# lichtenstein_onion.net
KiCad netlist of a schematic drawn in EAGLE
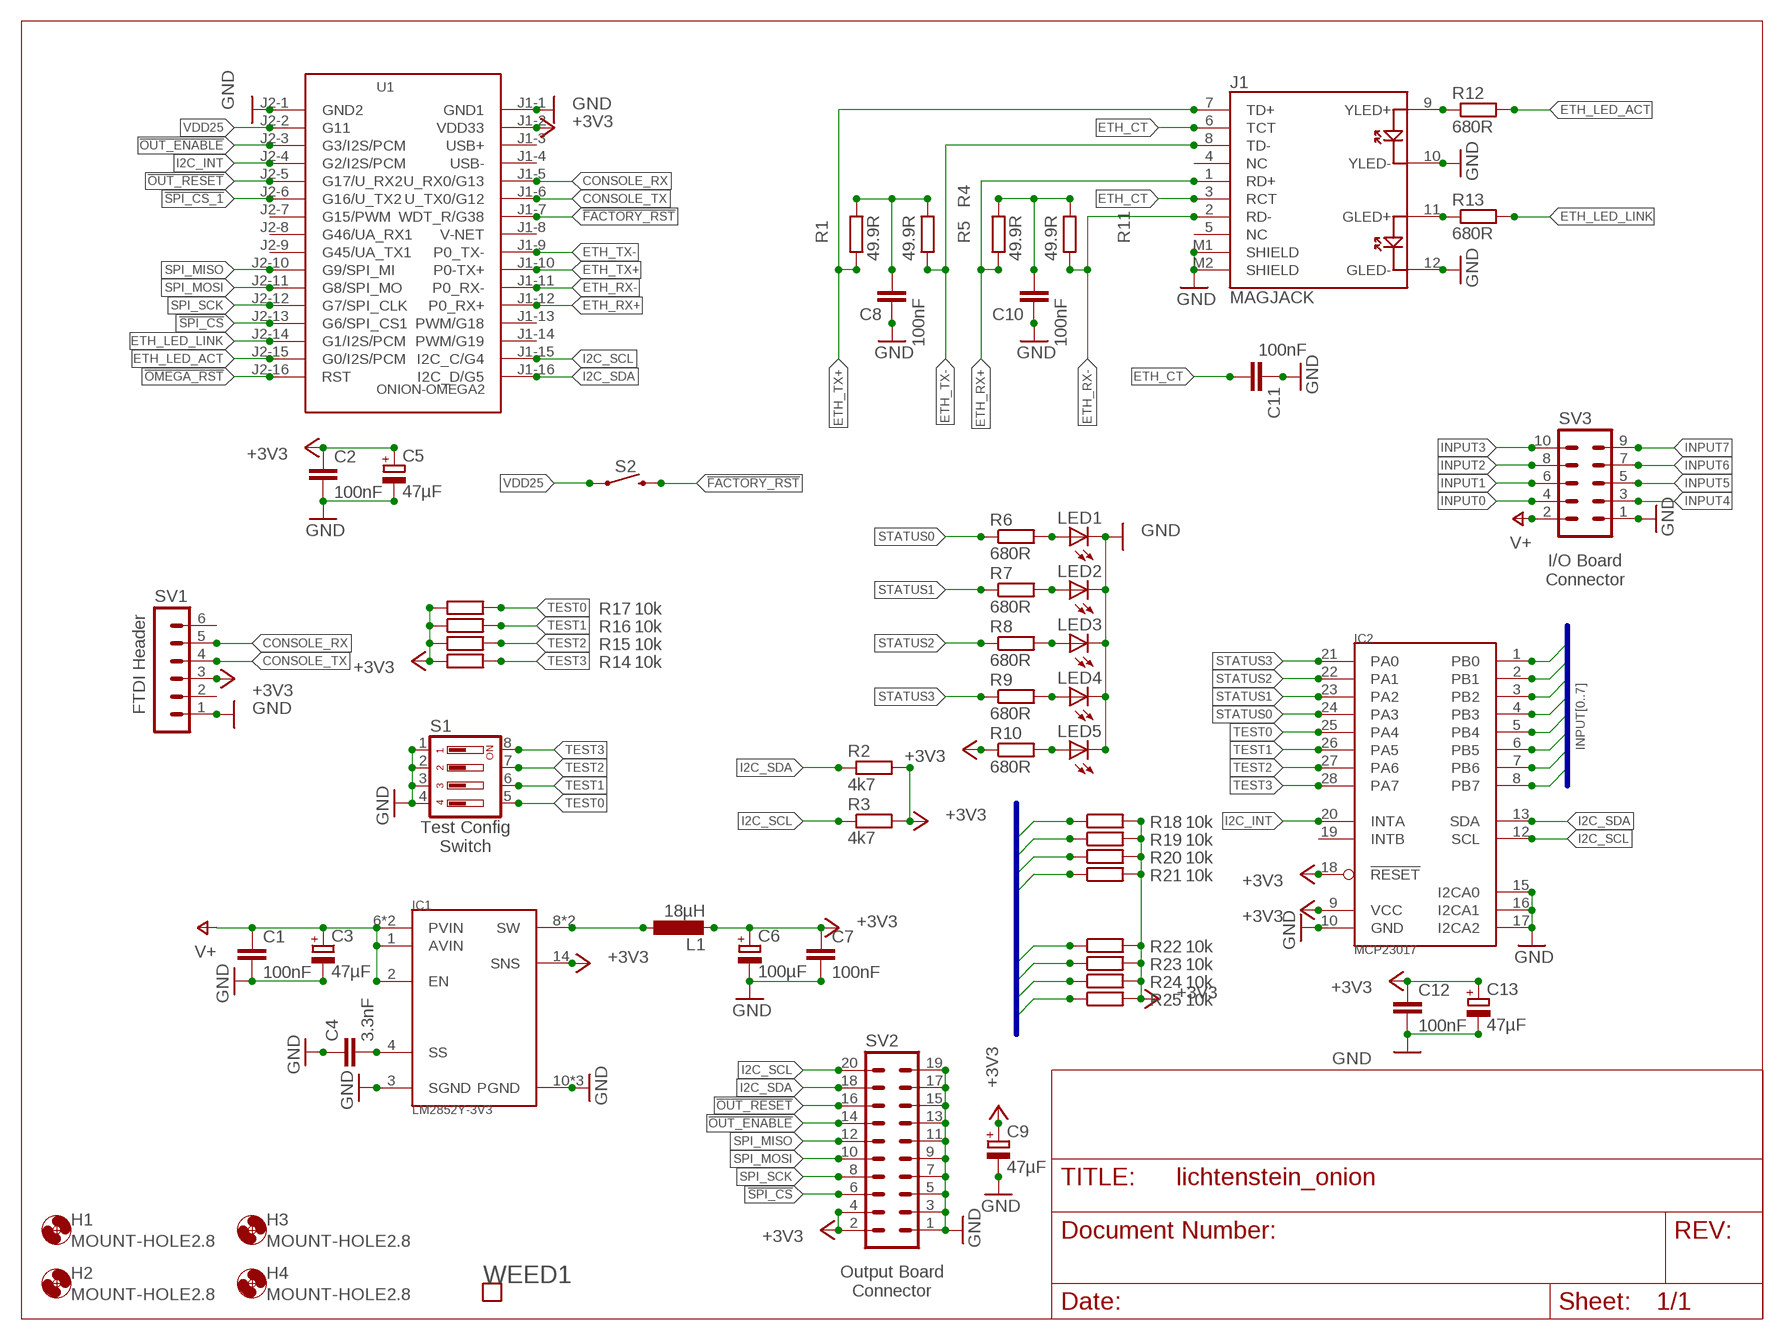
[diagram p0: schematic, sheet 1]

(export (version "E")
  (design (tool "Eeschema 10.0.6"))
  (components
    (comp (ref "C1")
      (value "100nF")
      (footprint "eagle-import:C0805")
      (libsource (lib "eagle-import") (part "C-EUC0805"))
    )
    (comp (ref "C2")
      (value "100nF")
      (footprint "eagle-import:C0805")
      (libsource (lib "eagle-import") (part "C-EUC0805"))
    )
    (comp (ref "C3")
      (value "47µF")
      (footprint "eagle-import:CT7343")
      (libsource (lib "eagle-import") (part "CPOL-EUCT7343"))
    )
    (comp (ref "C4")
      (value "3.3nF")
      (footprint "eagle-import:C0805")
      (libsource (lib "eagle-import") (part "C-EUC0805"))
    )
    (comp (ref "C5")
      (value "47µF")
      (footprint "eagle-import:CT7343")
      (libsource (lib "eagle-import") (part "CPOL-EUCT7343"))
    )
    (comp (ref "C6")
      (value "100µF")
      (footprint "eagle-import:CT7343")
      (libsource (lib "eagle-import") (part "CPOL-EUCT7343"))
    )
    (comp (ref "C7")
      (value "100nF")
      (footprint "eagle-import:C0805")
      (libsource (lib "eagle-import") (part "C-EUC0805"))
    )
    (comp (ref "C8")
      (value "100nF")
      (footprint "eagle-import:C0805")
      (libsource (lib "eagle-import") (part "C-EUC0805"))
    )
    (comp (ref "C9")
      (value "47µF")
      (footprint "eagle-import:SMC_D")
      (libsource (lib "eagle-import") (part "CPOL-EUSMCD"))
    )
    (comp (ref "C10")
      (value "100nF")
      (footprint "eagle-import:C0805")
      (libsource (lib "eagle-import") (part "C-EUC0805"))
    )
    (comp (ref "C11")
      (value "100nF")
      (footprint "eagle-import:C0805")
      (libsource (lib "eagle-import") (part "C-EUC0805"))
    )
    (comp (ref "C12")
      (value "100nF")
      (footprint "eagle-import:C0805")
      (libsource (lib "eagle-import") (part "C-EUC0805"))
    )
    (comp (ref "C13")
      (value "47µF")
      (footprint "eagle-import:CT7343")
      (libsource (lib "eagle-import") (part "CPOL-EUCT7343"))
    )
    (comp (ref "H1")
      (value "MOUNT-HOLE2.8")
      (footprint "eagle-import:2,8")
      (libsource (lib "eagle-import") (part "MOUNT-HOLE2.8"))
    )
    (comp (ref "H2")
      (value "MOUNT-HOLE2.8")
      (footprint "eagle-import:2,8")
      (libsource (lib "eagle-import") (part "MOUNT-HOLE2.8"))
    )
    (comp (ref "H3")
      (value "MOUNT-HOLE2.8")
      (footprint "eagle-import:2,8")
      (libsource (lib "eagle-import") (part "MOUNT-HOLE2.8"))
    )
    (comp (ref "H4")
      (value "MOUNT-HOLE2.8")
      (footprint "eagle-import:2,8")
      (libsource (lib "eagle-import") (part "MOUNT-HOLE2.8"))
    )
    (comp (ref "IC1")
      (value "LM2852Y-3V3")
      (footprint "eagle-import:HTSSOP14")
      (libsource (lib "eagle-import") (part "LM2852HTSSOP14"))
    )
    (comp (ref "IC2")
      (value "MCP23017")
      (footprint "eagle-import:SSOP28")
      (libsource (lib "eagle-import") (part "MCP23017SSOP28"))
    )
    (comp (ref "J1")
      (value "MAGJACK")
      (footprint "eagle-import:MAGJACK")
      (libsource (lib "eagle-import") (part "MAGJACK"))
    )
    (comp (ref "L1")
      (value "18µH")
      (footprint "eagle-import:SRR1050A")
      (libsource (lib "eagle-import") (part "SRR1050A"))
    )
    (comp (ref "LED1")
      (value "LEDCHIPLED_1206")
      (footprint "eagle-import:CHIPLED_1206")
      (libsource (lib "eagle-import") (part "LEDCHIPLED_1206"))
    )
    (comp (ref "LED2")
      (value "LEDCHIPLED_1206")
      (footprint "eagle-import:CHIPLED_1206")
      (libsource (lib "eagle-import") (part "LEDCHIPLED_1206"))
    )
    (comp (ref "LED3")
      (value "LEDCHIPLED_1206")
      (footprint "eagle-import:CHIPLED_1206")
      (libsource (lib "eagle-import") (part "LEDCHIPLED_1206"))
    )
    (comp (ref "LED4")
      (value "LEDCHIPLED_1206")
      (footprint "eagle-import:CHIPLED_1206")
      (libsource (lib "eagle-import") (part "LEDCHIPLED_1206"))
    )
    (comp (ref "LED5")
      (value "LEDCHIPLED_1206")
      (footprint "eagle-import:CHIPLED_1206")
      (libsource (lib "eagle-import") (part "LEDCHIPLED_1206"))
    )
    (comp (ref "R1")
      (value "49.9R")
      (footprint "eagle-import:M0805")
      (libsource (lib "eagle-import") (part "R-EU_M0805"))
    )
    (comp (ref "R2")
      (value "4k7")
      (footprint "eagle-import:M0805")
      (libsource (lib "eagle-import") (part "R-EU_M0805"))
    )
    (comp (ref "R3")
      (value "4k7")
      (footprint "eagle-import:M0805")
      (libsource (lib "eagle-import") (part "R-EU_M0805"))
    )
    (comp (ref "R4")
      (value "49.9R")
      (footprint "eagle-import:M0805")
      (libsource (lib "eagle-import") (part "R-EU_M0805"))
    )
    (comp (ref "R5")
      (value "49.9R")
      (footprint "eagle-import:M0805")
      (libsource (lib "eagle-import") (part "R-EU_M0805"))
    )
    (comp (ref "R6")
      (value "680R")
      (footprint "eagle-import:M0805")
      (libsource (lib "eagle-import") (part "R-EU_M0805"))
    )
    (comp (ref "R7")
      (value "680R")
      (footprint "eagle-import:M0805")
      (libsource (lib "eagle-import") (part "R-EU_M0805"))
    )
    (comp (ref "R8")
      (value "680R")
      (footprint "eagle-import:M0805")
      (libsource (lib "eagle-import") (part "R-EU_M0805"))
    )
    (comp (ref "R9")
      (value "680R")
      (footprint "eagle-import:M0805")
      (libsource (lib "eagle-import") (part "R-EU_M0805"))
    )
    (comp (ref "R10")
      (value "680R")
      (footprint "eagle-import:M0805")
      (libsource (lib "eagle-import") (part "R-EU_M0805"))
    )
    (comp (ref "R11")
      (value "49.9R")
      (footprint "eagle-import:M0805")
      (libsource (lib "eagle-import") (part "R-EU_M0805"))
    )
    (comp (ref "R12")
      (value "680R")
      (footprint "eagle-import:M0805")
      (libsource (lib "eagle-import") (part "R-EU_M0805"))
    )
    (comp (ref "R13")
      (value "680R")
      (footprint "eagle-import:M0805")
      (libsource (lib "eagle-import") (part "R-EU_M0805"))
    )
    (comp (ref "R14")
      (value "10k")
      (footprint "eagle-import:M0805")
      (libsource (lib "eagle-import") (part "R-EU_M0805"))
    )
    (comp (ref "R15")
      (value "10k")
      (footprint "eagle-import:M0805")
      (libsource (lib "eagle-import") (part "R-EU_M0805"))
    )
    (comp (ref "R16")
      (value "10k")
      (footprint "eagle-import:M0805")
      (libsource (lib "eagle-import") (part "R-EU_M0805"))
    )
    (comp (ref "R17")
      (value "10k")
      (footprint "eagle-import:M0805")
      (libsource (lib "eagle-import") (part "R-EU_M0805"))
    )
    (comp (ref "R18")
      (value "10k")
      (footprint "eagle-import:M0805")
      (libsource (lib "eagle-import") (part "R-EU_M0805"))
    )
    (comp (ref "R19")
      (value "10k")
      (footprint "eagle-import:M0805")
      (libsource (lib "eagle-import") (part "R-EU_M0805"))
    )
    (comp (ref "R20")
      (value "10k")
      (footprint "eagle-import:M0805")
      (libsource (lib "eagle-import") (part "R-EU_M0805"))
    )
    (comp (ref "R21")
      (value "10k")
      (footprint "eagle-import:M0805")
      (libsource (lib "eagle-import") (part "R-EU_M0805"))
    )
    (comp (ref "R22")
      (value "10k")
      (footprint "eagle-import:M0805")
      (libsource (lib "eagle-import") (part "R-EU_M0805"))
    )
    (comp (ref "R23")
      (value "10k")
      (footprint "eagle-import:M0805")
      (libsource (lib "eagle-import") (part "R-EU_M0805"))
    )
    (comp (ref "R24")
      (value "10k")
      (footprint "eagle-import:M0805")
      (libsource (lib "eagle-import") (part "R-EU_M0805"))
    )
    (comp (ref "R25")
      (value "10k")
      (footprint "eagle-import:M0805")
      (libsource (lib "eagle-import") (part "R-EU_M0805"))
    )
    (comp (ref "S1")
      (value "219-04")
      (footprint "eagle-import:CTS-219-04")
      (libsource (lib "eagle-import") (part "219-04"))
    )
    (comp (ref "S2")
      (value "MOMENTARY-SWITCH-SPST-PTH-6.0MM")
      (footprint "eagle-import:TACTILE_SWITCH_PTH_6.0MM")
      (libsource (lib "eagle-import") (part "MOMENTARY-SWITCH-SPST-PTH-6.0MM"))
    )
    (comp (ref "SV1")
      (value "MA06-1")
      (footprint "eagle-import:MA06-1")
      (libsource (lib "eagle-import") (part "MA06-1"))
    )
    (comp (ref "SV2")
      (value "MA10-2")
      (footprint "eagle-import:MA10-2")
      (libsource (lib "eagle-import") (part "MA10-2"))
    )
    (comp (ref "SV3")
      (value "MA05-2")
      (footprint "eagle-import:MA05-2")
      (libsource (lib "eagle-import") (part "MA05-2"))
    )
    (comp (ref "U1")
      (value "ONION-OMEGA2")
      (footprint "eagle-import:ONION-2MM-2X16")
      (libsource (lib "eagle-import") (part "ONION-OMEGA2"))
    )
    (comp (ref "WEED1")
      (value "WEED")
      (footprint "eagle-import:DOINK")
      (libsource (lib "eagle-import") (part "WEED"))
    )
  )
  (nets
    (net (code "1") (name "+3V3") (class "Default")
      (node (ref "C12") (pin "1") (pinfunction "1_1") (pintype "passive"))
      (node (ref "C13") (pin "+") (pinfunction "+_+") (pintype "passive"))
      (node (ref "C2") (pin "1") (pinfunction "1_1") (pintype "passive"))
      (node (ref "C5") (pin "+") (pinfunction "+_+") (pintype "passive"))
      (node (ref "C6") (pin "+") (pinfunction "+_+") (pintype "passive"))
      (node (ref "C7") (pin "1") (pinfunction "1_1") (pintype "passive"))
      (node (ref "C9") (pin "+") (pinfunction "+_+") (pintype "passive"))
      (node (ref "IC1") (pin "14") (pinfunction "SNS_14") (pintype "bidirectional"))
      (node (ref "IC2") (pin "18") (pinfunction "~{RESET}_18") (pintype "input"))
      (node (ref "IC2") (pin "9") (pinfunction "VCC_9") (pintype "power_in"))
      (node (ref "L1") (pin "P$2") (pinfunction "2_P$2") (pintype "passive"))
      (node (ref "R10") (pin "1") (pinfunction "1_1") (pintype "passive"))
      (node (ref "R14") (pin "1") (pinfunction "1_1") (pintype "passive"))
      (node (ref "R15") (pin "1") (pinfunction "1_1") (pintype "passive"))
      (node (ref "R16") (pin "1") (pinfunction "1_1") (pintype "passive"))
      (node (ref "R17") (pin "1") (pinfunction "1_1") (pintype "passive"))
      (node (ref "R18") (pin "2") (pinfunction "2_2") (pintype "passive"))
      (node (ref "R19") (pin "2") (pinfunction "2_2") (pintype "passive"))
      (node (ref "R2") (pin "2") (pinfunction "2_2") (pintype "passive"))
      (node (ref "R20") (pin "2") (pinfunction "2_2") (pintype "passive"))
      (node (ref "R21") (pin "2") (pinfunction "2_2") (pintype "passive"))
      (node (ref "R22") (pin "2") (pinfunction "2_2") (pintype "passive"))
      (node (ref "R23") (pin "2") (pinfunction "2_2") (pintype "passive"))
      (node (ref "R24") (pin "2") (pinfunction "2_2") (pintype "passive"))
      (node (ref "R25") (pin "2") (pinfunction "2_2") (pintype "passive"))
      (node (ref "R3") (pin "2") (pinfunction "2_2") (pintype "passive"))
      (node (ref "SV1") (pin "3") (pinfunction "3_3") (pintype "passive"))
      (node (ref "SV2") (pin "2") (pinfunction "2_2") (pintype "passive"))
      (node (ref "SV2") (pin "4") (pinfunction "4_4") (pintype "passive"))
      (node (ref "U1") (pin "J1-2") (pinfunction "VDD33_J1-2") (pintype "bidirectional"))
    )
    (net (code "3") (name "/~{FACTORY_RST}") (class "Default")
      (node (ref "S2") (pin "3") (pinfunction "2_3") (pintype "passive"))
      (node (ref "U1") (pin "J1-7") (pinfunction "WDT_R/G38_J1-7") (pintype "bidirectional"))
    )
    (net (code "4") (name "/~{OMEGA_RST}") (class "Default")
      (node (ref "U1") (pin "J2-16") (pinfunction "RST_J2-16") (pintype "bidirectional"))
    )
    (net (code "5") (name "/~{OUT_ENABLE}") (class "Default")
      (node (ref "SV2") (pin "14") (pinfunction "14_14") (pintype "passive"))
      (node (ref "U1") (pin "J2-3") (pinfunction "G3/I2S/PCM_J2-3") (pintype "bidirectional"))
    )
    (net (code "6") (name "/~{OUT_RESET}") (class "Default")
      (node (ref "SV2") (pin "16") (pinfunction "16_16") (pintype "passive"))
      (node (ref "U1") (pin "J2-5") (pinfunction "G17/U_RX2_J2-5") (pintype "bidirectional"))
    )
    (net (code "7") (name "/~{SPI_CS_1}") (class "Default")
      (node (ref "U1") (pin "J2-6") (pinfunction "G16/U_TX2_J2-6") (pintype "bidirectional"))
    )
    (net (code "8") (name "/~{SPI_CS}") (class "Default")
      (node (ref "SV2") (pin "6") (pinfunction "6_6") (pintype "passive"))
      (node (ref "U1") (pin "J2-13") (pinfunction "G6/SPI_CS1_J2-13") (pintype "bidirectional"))
    )
    (net (code "9") (name "CONSOLE_RX") (class "Default")
      (node (ref "SV1") (pin "5") (pinfunction "5_5") (pintype "passive"))
      (node (ref "U1") (pin "J1-5") (pinfunction "U_RX0/G13_J1-5") (pintype "bidirectional"))
    )
    (net (code "10") (name "CONSOLE_TX") (class "Default")
      (node (ref "SV1") (pin "4") (pinfunction "4_4") (pintype "passive"))
      (node (ref "U1") (pin "J1-6") (pinfunction "U_TX0/G12_J1-6") (pintype "bidirectional"))
    )
    (net (code "11") (name "ETH_CT") (class "Default")
      (node (ref "C11") (pin "2") (pinfunction "2_2") (pintype "passive"))
      (node (ref "J1") (pin "3") (pinfunction "RCT_3") (pintype "bidirectional"))
      (node (ref "J1") (pin "6") (pinfunction "TCT_6") (pintype "bidirectional"))
    )
    (net (code "12") (name "ETH_LED_ACT") (class "Default")
      (node (ref "R12") (pin "2") (pinfunction "2_2") (pintype "passive"))
      (node (ref "U1") (pin "J2-15") (pinfunction "G0/I2S/PCM_J2-15") (pintype "bidirectional"))
    )
    (net (code "13") (name "ETH_LED_LINK") (class "Default")
      (node (ref "R13") (pin "2") (pinfunction "2_2") (pintype "passive"))
      (node (ref "U1") (pin "J2-14") (pinfunction "G1/I2S/PCM_J2-14") (pintype "bidirectional"))
    )
    (net (code "14") (name "ETH_RX+") (class "Default")
      (node (ref "J1") (pin "1") (pinfunction "RD+_1") (pintype "bidirectional"))
      (node (ref "R5") (pin "1") (pinfunction "1_1") (pintype "passive"))
      (node (ref "U1") (pin "J1-12") (pinfunction "P0_RX+_J1-12") (pintype "bidirectional"))
    )
    (net (code "15") (name "ETH_RX-") (class "Default")
      (node (ref "J1") (pin "2") (pinfunction "RD-_2") (pintype "bidirectional"))
      (node (ref "R11") (pin "1") (pinfunction "1_1") (pintype "passive"))
      (node (ref "U1") (pin "J1-11") (pinfunction "P0_RX-_J1-11") (pintype "bidirectional"))
    )
    (net (code "16") (name "ETH_TX+") (class "Default")
      (node (ref "J1") (pin "7") (pinfunction "TD+_7") (pintype "bidirectional"))
      (node (ref "R1") (pin "1") (pinfunction "1_1") (pintype "passive"))
      (node (ref "U1") (pin "J1-10") (pinfunction "P0-TX+_J1-10") (pintype "bidirectional"))
    )
    (net (code "17") (name "ETH_TX-") (class "Default")
      (node (ref "J1") (pin "8") (pinfunction "TD-_8") (pintype "bidirectional"))
      (node (ref "R4") (pin "1") (pinfunction "1_1") (pintype "passive"))
      (node (ref "U1") (pin "J1-9") (pinfunction "P0_TX-_J1-9") (pintype "bidirectional"))
    )
    (net (code "18") (name "GND") (class "Default")
      (node (ref "C1") (pin "2") (pinfunction "2_2") (pintype "passive"))
      (node (ref "C10") (pin "1") (pinfunction "1_1") (pintype "passive"))
      (node (ref "C11") (pin "1") (pinfunction "1_1") (pintype "passive"))
      (node (ref "C12") (pin "2") (pinfunction "2_2") (pintype "passive"))
      (node (ref "C13") (pin "-") (pinfunction "-_-") (pintype "passive"))
      (node (ref "C2") (pin "2") (pinfunction "2_2") (pintype "passive"))
      (node (ref "C3") (pin "-") (pinfunction "-_-") (pintype "passive"))
      (node (ref "C4") (pin "1") (pinfunction "1_1") (pintype "passive"))
      (node (ref "C5") (pin "-") (pinfunction "-_-") (pintype "passive"))
      (node (ref "C6") (pin "-") (pinfunction "-_-") (pintype "passive"))
      (node (ref "C7") (pin "2") (pinfunction "2_2") (pintype "passive"))
      (node (ref "C8") (pin "1") (pinfunction "1_1") (pintype "passive"))
      (node (ref "C9") (pin "-") (pinfunction "-_-") (pintype "passive"))
      (node (ref "IC1") (pin "10") (pinfunction "PGND_10") (pintype "power_in"))
      (node (ref "IC1") (pin "11") (pinfunction "PGND_11") (pintype "power_in"))
      (node (ref "IC1") (pin "3") (pinfunction "SGND_3") (pintype "power_in"))
      (node (ref "IC1") (pin "PAD") (pinfunction "PGND_PAD") (pintype "power_in"))
      (node (ref "IC2") (pin "10") (pinfunction "GND_10") (pintype "power_in"))
      (node (ref "IC2") (pin "15") (pinfunction "I2CA0_15") (pintype "bidirectional"))
      (node (ref "IC2") (pin "16") (pinfunction "I2CA1_16") (pintype "bidirectional"))
      (node (ref "IC2") (pin "17") (pinfunction "I2CA2_17") (pintype "bidirectional"))
      (node (ref "J1") (pin "10") (pinfunction "YLED-_10") (pintype "bidirectional"))
      (node (ref "J1") (pin "12") (pinfunction "GLED-_12") (pintype "bidirectional"))
      (node (ref "J1") (pin "M1") (pinfunction "SHIELD_M1") (pintype "bidirectional"))
      (node (ref "J1") (pin "M2") (pinfunction "SHIELD_M2") (pintype "bidirectional"))
      (node (ref "LED1") (pin "C") (pinfunction "C_C") (pintype "passive"))
      (node (ref "LED2") (pin "C") (pinfunction "C_C") (pintype "passive"))
      (node (ref "LED3") (pin "C") (pinfunction "C_C") (pintype "passive"))
      (node (ref "LED4") (pin "C") (pinfunction "C_C") (pintype "passive"))
      (node (ref "LED5") (pin "C") (pinfunction "C_C") (pintype "passive"))
      (node (ref "S1") (pin "1") (pinfunction "1_1") (pintype "passive"))
      (node (ref "S1") (pin "2") (pinfunction "2_2") (pintype "passive"))
      (node (ref "S1") (pin "3") (pinfunction "3_3") (pintype "passive"))
      (node (ref "S1") (pin "4") (pinfunction "4_4") (pintype "passive"))
      (node (ref "SV1") (pin "1") (pinfunction "1_1") (pintype "passive"))
      (node (ref "SV2") (pin "1") (pinfunction "1_1") (pintype "passive"))
      (node (ref "SV2") (pin "11") (pinfunction "11_11") (pintype "passive"))
      (node (ref "SV2") (pin "13") (pinfunction "13_13") (pintype "passive"))
      (node (ref "SV2") (pin "15") (pinfunction "15_15") (pintype "passive"))
      (node (ref "SV2") (pin "17") (pinfunction "17_17") (pintype "passive"))
      (node (ref "SV2") (pin "19") (pinfunction "19_19") (pintype "passive"))
      (node (ref "SV2") (pin "3") (pinfunction "3_3") (pintype "passive"))
      (node (ref "SV2") (pin "5") (pinfunction "5_5") (pintype "passive"))
      (node (ref "SV2") (pin "7") (pinfunction "7_7") (pintype "passive"))
      (node (ref "SV2") (pin "9") (pinfunction "9_9") (pintype "passive"))
      (node (ref "SV3") (pin "1") (pinfunction "1_1") (pintype "passive"))
      (node (ref "U1") (pin "J1-1") (pinfunction "GND1_J1-1") (pintype "bidirectional"))
      (node (ref "U1") (pin "J2-1") (pinfunction "GND2_J2-1") (pintype "bidirectional"))
    )
    (net (code "19") (name "I2C_INT") (class "Default")
      (node (ref "IC2") (pin "20") (pinfunction "INTA_20") (pintype "output"))
      (node (ref "U1") (pin "J2-4") (pinfunction "G2/I2S/PCM_J2-4") (pintype "bidirectional"))
    )
    (net (code "20") (name "I2C_SCL") (class "Default")
      (node (ref "IC2") (pin "12") (pinfunction "SCL_12") (pintype "bidirectional"))
      (node (ref "R3") (pin "1") (pinfunction "1_1") (pintype "passive"))
      (node (ref "SV2") (pin "20") (pinfunction "20_20") (pintype "passive"))
      (node (ref "U1") (pin "J1-15") (pinfunction "I2C_C/G4_J1-15") (pintype "bidirectional"))
    )
    (net (code "21") (name "I2C_SDA") (class "Default")
      (node (ref "IC2") (pin "13") (pinfunction "SDA_13") (pintype "bidirectional"))
      (node (ref "R2") (pin "1") (pinfunction "1_1") (pintype "passive"))
      (node (ref "SV2") (pin "18") (pinfunction "18_18") (pintype "passive"))
      (node (ref "U1") (pin "J1-16") (pinfunction "I2C_D/G5_J1-16") (pintype "bidirectional"))
    )
    (net (code "22") (name "INPUT0") (class "Default")
      (node (ref "IC2") (pin "2") (pinfunction "PB1_2") (pintype "bidirectional"))
      (node (ref "R18") (pin "1") (pinfunction "1_1") (pintype "passive"))
      (node (ref "SV3") (pin "4") (pinfunction "4_4") (pintype "passive"))
    )
    (net (code "23") (name "INPUT1") (class "Default")
      (node (ref "IC2") (pin "4") (pinfunction "PB3_4") (pintype "bidirectional"))
      (node (ref "R19") (pin "1") (pinfunction "1_1") (pintype "passive"))
      (node (ref "SV3") (pin "6") (pinfunction "6_6") (pintype "passive"))
    )
    (net (code "24") (name "INPUT2") (class "Default")
      (node (ref "IC2") (pin "6") (pinfunction "PB5_6") (pintype "bidirectional"))
      (node (ref "R24") (pin "1") (pinfunction "1_1") (pintype "passive"))
      (node (ref "SV3") (pin "8") (pinfunction "8_8") (pintype "passive"))
    )
    (net (code "25") (name "INPUT3") (class "Default")
      (node (ref "IC2") (pin "8") (pinfunction "PB7_8") (pintype "bidirectional"))
      (node (ref "R25") (pin "1") (pinfunction "1_1") (pintype "passive"))
      (node (ref "SV3") (pin "10") (pinfunction "10_10") (pintype "passive"))
    )
    (net (code "26") (name "INPUT4") (class "Default")
      (node (ref "IC2") (pin "1") (pinfunction "PB0_1") (pintype "bidirectional"))
      (node (ref "R20") (pin "1") (pinfunction "1_1") (pintype "passive"))
      (node (ref "SV3") (pin "3") (pinfunction "3_3") (pintype "passive"))
    )
    (net (code "27") (name "INPUT5") (class "Default")
      (node (ref "IC2") (pin "3") (pinfunction "PB2_3") (pintype "bidirectional"))
      (node (ref "R21") (pin "1") (pinfunction "1_1") (pintype "passive"))
      (node (ref "SV3") (pin "5") (pinfunction "5_5") (pintype "passive"))
    )
    (net (code "28") (name "INPUT6") (class "Default")
      (node (ref "IC2") (pin "5") (pinfunction "PB4_5") (pintype "bidirectional"))
      (node (ref "R23") (pin "1") (pinfunction "1_1") (pintype "passive"))
      (node (ref "SV3") (pin "7") (pinfunction "7_7") (pintype "passive"))
    )
    (net (code "29") (name "INPUT7") (class "Default")
      (node (ref "IC2") (pin "7") (pinfunction "PB6_7") (pintype "bidirectional"))
      (node (ref "R22") (pin "1") (pinfunction "1_1") (pintype "passive"))
      (node (ref "SV3") (pin "9") (pinfunction "9_9") (pintype "passive"))
    )
    (net (code "30") (name "Net-(C8-Pad2)") (class "Default")
      (node (ref "C8") (pin "2") (pinfunction "2_2") (pintype "passive"))
      (node (ref "R1") (pin "2") (pinfunction "2_2") (pintype "passive"))
      (node (ref "R4") (pin "2") (pinfunction "2_2") (pintype "passive"))
    )
    (net (code "31") (name "Net-(C10-Pad2)") (class "Default")
      (node (ref "C10") (pin "2") (pinfunction "2_2") (pintype "passive"))
      (node (ref "R11") (pin "2") (pinfunction "2_2") (pintype "passive"))
      (node (ref "R5") (pin "2") (pinfunction "2_2") (pintype "passive"))
    )
    (net (code "32") (name "Net-(IC1-SS)") (class "Default")
      (node (ref "C4") (pin "2") (pinfunction "2_2") (pintype "passive"))
      (node (ref "IC1") (pin "4") (pinfunction "SS_4") (pintype "bidirectional"))
    )
    (net (code "33") (name "Net-(J1-GLED+)") (class "Default")
      (node (ref "J1") (pin "11") (pinfunction "GLED+_11") (pintype "bidirectional"))
      (node (ref "R13") (pin "1") (pinfunction "1_1") (pintype "passive"))
    )
    (net (code "34") (name "Net-(J1-YLED+)") (class "Default")
      (node (ref "J1") (pin "9") (pinfunction "YLED+_9") (pintype "bidirectional"))
      (node (ref "R12") (pin "1") (pinfunction "1_1") (pintype "passive"))
    )
    (net (code "35") (name "Net-(L1-1)") (class "Default")
      (node (ref "IC1") (pin "8") (pinfunction "SW_8") (pintype "bidirectional"))
      (node (ref "IC1") (pin "9") (pinfunction "SW_9") (pintype "bidirectional"))
      (node (ref "L1") (pin "P$1") (pinfunction "1_P$1") (pintype "passive"))
    )
    (net (code "36") (name "Net-(LED1-PadA)") (class "Default")
      (node (ref "LED1") (pin "A") (pinfunction "A_A") (pintype "passive"))
      (node (ref "R6") (pin "2") (pinfunction "2_2") (pintype "passive"))
    )
    (net (code "37") (name "Net-(LED2-PadA)") (class "Default")
      (node (ref "LED2") (pin "A") (pinfunction "A_A") (pintype "passive"))
      (node (ref "R7") (pin "2") (pinfunction "2_2") (pintype "passive"))
    )
    (net (code "38") (name "Net-(LED3-PadA)") (class "Default")
      (node (ref "LED3") (pin "A") (pinfunction "A_A") (pintype "passive"))
      (node (ref "R8") (pin "2") (pinfunction "2_2") (pintype "passive"))
    )
    (net (code "39") (name "Net-(LED4-PadA)") (class "Default")
      (node (ref "LED4") (pin "A") (pinfunction "A_A") (pintype "passive"))
      (node (ref "R9") (pin "2") (pinfunction "2_2") (pintype "passive"))
    )
    (net (code "40") (name "Net-(LED5-PadA)") (class "Default")
      (node (ref "LED5") (pin "A") (pinfunction "A_A") (pintype "passive"))
      (node (ref "R10") (pin "2") (pinfunction "2_2") (pintype "passive"))
    )
    (net (code "41") (name "SPI_MISO") (class "Default")
      (node (ref "SV2") (pin "12") (pinfunction "12_12") (pintype "passive"))
      (node (ref "U1") (pin "J2-10") (pinfunction "G9/SPI_MI_J2-10") (pintype "bidirectional"))
    )
    (net (code "42") (name "SPI_MOSI") (class "Default")
      (node (ref "SV2") (pin "10") (pinfunction "10_10") (pintype "passive"))
      (node (ref "U1") (pin "J2-11") (pinfunction "G8/SPI_MO_J2-11") (pintype "bidirectional"))
    )
    (net (code "43") (name "SPI_SCK") (class "Default")
      (node (ref "SV2") (pin "8") (pinfunction "8_8") (pintype "passive"))
      (node (ref "U1") (pin "J2-12") (pinfunction "G7/SPI_CLK_J2-12") (pintype "bidirectional"))
    )
    (net (code "44") (name "STATUS0") (class "Default")
      (node (ref "IC2") (pin "24") (pinfunction "PA3_24") (pintype "bidirectional"))
      (node (ref "R6") (pin "1") (pinfunction "1_1") (pintype "passive"))
    )
    (net (code "45") (name "STATUS1") (class "Default")
      (node (ref "IC2") (pin "23") (pinfunction "PA2_23") (pintype "bidirectional"))
      (node (ref "R7") (pin "1") (pinfunction "1_1") (pintype "passive"))
    )
    (net (code "46") (name "STATUS2") (class "Default")
      (node (ref "IC2") (pin "22") (pinfunction "PA1_22") (pintype "bidirectional"))
      (node (ref "R8") (pin "1") (pinfunction "1_1") (pintype "passive"))
    )
    (net (code "47") (name "STATUS3") (class "Default")
      (node (ref "IC2") (pin "21") (pinfunction "PA0_21") (pintype "bidirectional"))
      (node (ref "R9") (pin "1") (pinfunction "1_1") (pintype "passive"))
    )
    (net (code "48") (name "TEST0") (class "Default")
      (node (ref "IC2") (pin "25") (pinfunction "PA4_25") (pintype "bidirectional"))
      (node (ref "R17") (pin "2") (pinfunction "2_2") (pintype "passive"))
      (node (ref "S1") (pin "5") (pinfunction "5_5") (pintype "passive"))
    )
    (net (code "49") (name "TEST1") (class "Default")
      (node (ref "IC2") (pin "26") (pinfunction "PA5_26") (pintype "bidirectional"))
      (node (ref "R16") (pin "2") (pinfunction "2_2") (pintype "passive"))
      (node (ref "S1") (pin "6") (pinfunction "6_6") (pintype "passive"))
    )
    (net (code "50") (name "TEST2") (class "Default")
      (node (ref "IC2") (pin "27") (pinfunction "PA6_27") (pintype "bidirectional"))
      (node (ref "R15") (pin "2") (pinfunction "2_2") (pintype "passive"))
      (node (ref "S1") (pin "7") (pinfunction "7_7") (pintype "passive"))
    )
    (net (code "51") (name "TEST3") (class "Default")
      (node (ref "IC2") (pin "28") (pinfunction "PA7_28") (pintype "bidirectional"))
      (node (ref "R14") (pin "2") (pinfunction "2_2") (pintype "passive"))
      (node (ref "S1") (pin "8") (pinfunction "8_8") (pintype "passive"))
    )
    (net (code "52") (name "V+") (class "Default")
      (node (ref "C1") (pin "1") (pinfunction "1_1") (pintype "passive"))
      (node (ref "C3") (pin "+") (pinfunction "+_+") (pintype "passive"))
      (node (ref "IC1") (pin "1") (pinfunction "AVIN_1") (pintype "power_in"))
      (node (ref "IC1") (pin "2") (pinfunction "EN_2") (pintype "input"))
      (node (ref "IC1") (pin "6") (pinfunction "PVIN_6") (pintype "power_in"))
      (node (ref "IC1") (pin "7") (pinfunction "PVIN_7") (pintype "power_in"))
      (node (ref "SV3") (pin "2") (pinfunction "2_2") (pintype "passive"))
    )
    (net (code "53") (name "VDD25") (class "Default")
      (node (ref "S2") (pin "1") (pinfunction "1_1") (pintype "passive"))
      (node (ref "U1") (pin "J2-2") (pinfunction "G11_J2-2") (pintype "bidirectional"))
    )
    (net (code "54") (name "unconnected-(IC2-INTB-Pad19)") (class "Default")
      (node (ref "IC2") (pin "19") (pinfunction "INTB_19") (pintype "output"))
    )
    (net (code "55") (name "unconnected-(J1-NC-Pad4)") (class "Default")
      (node (ref "J1") (pin "4") (pinfunction "NC_4") (pintype "bidirectional"))
    )
    (net (code "56") (name "unconnected-(J1-NC-Pad5)") (class "Default")
      (node (ref "J1") (pin "5") (pinfunction "NC_5") (pintype "bidirectional"))
    )
    (net (code "57") (name "unconnected-(SV1-Pad2)") (class "Default")
      (node (ref "SV1") (pin "2") (pinfunction "2_2") (pintype "passive"))
    )
    (net (code "58") (name "unconnected-(SV1-Pad6)") (class "Default")
      (node (ref "SV1") (pin "6") (pinfunction "6_6") (pintype "passive"))
    )
    (net (code "59") (name "unconnected-(U1-G15{slash}PWM-PadJ2-7)") (class "Default")
      (node (ref "U1") (pin "J2-7") (pinfunction "G15/PWM_J2-7") (pintype "bidirectional"))
    )
    (net (code "60") (name "unconnected-(U1-G45{slash}UA_TX1-PadJ2-9)") (class "Default")
      (node (ref "U1") (pin "J2-9") (pinfunction "G45/UA_TX1_J2-9") (pintype "bidirectional"))
    )
    (net (code "61") (name "unconnected-(U1-G46{slash}UA_RX1-PadJ2-8)") (class "Default")
      (node (ref "U1") (pin "J2-8") (pinfunction "G46/UA_RX1_J2-8") (pintype "bidirectional"))
    )
    (net (code "62") (name "unconnected-(U1-PWM{slash}G18-PadJ1-13)") (class "Default")
      (node (ref "U1") (pin "J1-13") (pinfunction "PWM/G18_J1-13") (pintype "bidirectional"))
    )
    (net (code "63") (name "unconnected-(U1-PWM{slash}G19-PadJ1-14)") (class "Default")
      (node (ref "U1") (pin "J1-14") (pinfunction "PWM/G19_J1-14") (pintype "bidirectional"))
    )
    (net (code "64") (name "unconnected-(U1-USB+-PadJ1-3)") (class "Default")
      (node (ref "U1") (pin "J1-3") (pinfunction "USB+_J1-3") (pintype "bidirectional"))
    )
    (net (code "65") (name "unconnected-(U1-USB--PadJ1-4)") (class "Default")
      (node (ref "U1") (pin "J1-4") (pinfunction "USB-_J1-4") (pintype "bidirectional"))
    )
    (net (code "66") (name "unconnected-(U1-V-NET-PadJ1-8)") (class "Default")
      (node (ref "U1") (pin "J1-8") (pinfunction "V-NET_J1-8") (pintype "bidirectional"))
    )
  )
)
